# Branly_Pi_v2.net
KiCad netlist of a schematic drawn in EAGLE
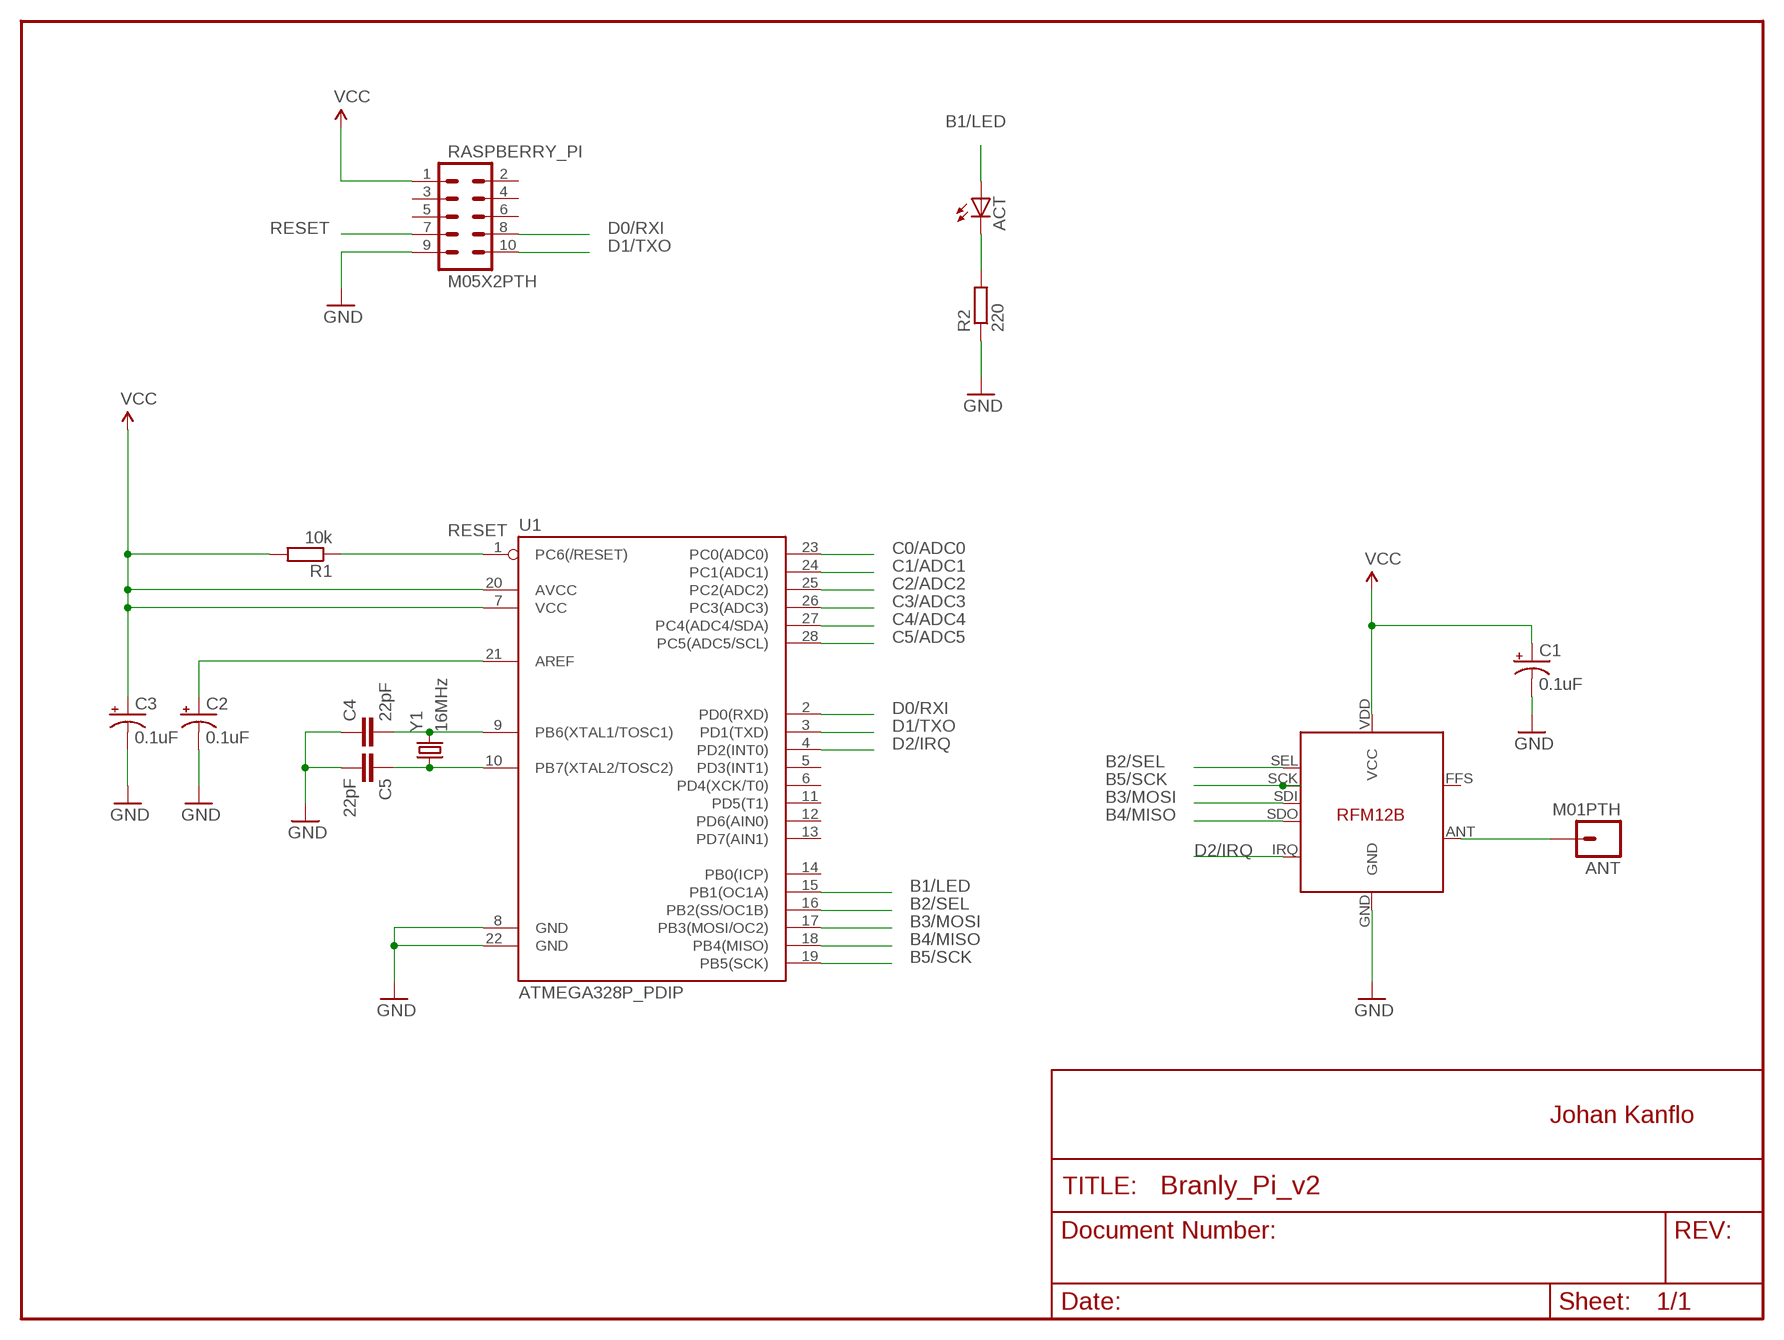
[diagram p0: schematic, sheet 1]

(export (version "E")
  (design (tool "Eeschema 10.0.6"))
  (components
    (comp (ref "ACT")
      (value "LED5MM")
      (footprint "eagle-import:LED5MM")
      (libsource (lib "eagle-import") (part "LED5MM"))
    )
    (comp (ref "ANT")
      (value "M01PTH")
      (footprint "eagle-import:1X01")
      (libsource (lib "eagle-import") (part "M01PTH"))
    )
    (comp (ref "C1")
      (value "0.1uF")
      (footprint "eagle-import:CPOL-RADIAL-10UF-25V")
      (libsource (lib "eagle-import") (part "CAP_POLPTH2"))
    )
    (comp (ref "C2")
      (value "0.1uF")
      (footprint "eagle-import:CPOL-RADIAL-10UF-25V")
      (libsource (lib "eagle-import") (part "CAP_POLPTH2"))
    )
    (comp (ref "C3")
      (value "0.1uF")
      (footprint "eagle-import:CPOL-RADIAL-10UF-25V")
      (libsource (lib "eagle-import") (part "CAP_POLPTH2"))
    )
    (comp (ref "C4")
      (value "22pF")
      (footprint "eagle-import:CAP-PTH-SMALL2")
      (libsource (lib "eagle-import") (part "CAPPTH2"))
    )
    (comp (ref "C5")
      (value "22pF")
      (footprint "eagle-import:CAP-PTH-SMALL2")
      (libsource (lib "eagle-import") (part "CAPPTH2"))
    )
    (comp (ref "R1")
      (value "10k")
      (footprint "eagle-import:0207_7")
      (libsource (lib "eagle-import") (part "R-EU_0207/7"))
    )
    (comp (ref "R2")
      (value "220")
      (footprint "eagle-import:0207_7")
      (libsource (lib "eagle-import") (part "R-EU_0207/7"))
    )
    (comp (ref "RASPBERRY_PI")
      (value "M05X2PTH")
      (footprint "eagle-import:AVR_ICSP")
      (libsource (lib "eagle-import") (part "M05X2PTH"))
    )
    (comp (ref "U1")
      (value "ATMEGA328P_PDIP")
      (footprint "eagle-import:DIL28-3")
      (libsource (lib "eagle-import") (part "ATMEGA328P_PDIP"))
    )
    (comp (ref "U2")
      (value "RFM12B")
      (footprint "eagle-import:RFM12B")
      (libsource (lib "eagle-import") (part "RFM12B"))
    )
    (comp (ref "Y1")
      (value "16MHz")
      (footprint "eagle-import:HC49US")
      (libsource (lib "eagle-import") (part "CRYSTALHC49US"))
    )
  )
  (nets
    (net (code "1") (name "/B1{slash}LED") (class "Default")
      (node (ref "ACT") (pin "A") (pinfunction "A_A") (pintype "passive"))
      (node (ref "U1") (pin "15") (pinfunction "PB1(OC1A)_15") (pintype "bidirectional"))
    )
    (net (code "2") (name "/B2{slash}SEL") (class "Default")
      (node (ref "U1") (pin "16") (pinfunction "PB2(SS/OC1B)_16") (pintype "bidirectional"))
      (node (ref "U2") (pin "SEL") (pinfunction "SEL_SEL") (pintype "input"))
    )
    (net (code "3") (name "/B3{slash}MOSI") (class "Default")
      (node (ref "U1") (pin "17") (pinfunction "PB3(MOSI/OC2)_17") (pintype "bidirectional"))
      (node (ref "U2") (pin "SDI") (pinfunction "SDI_SDI") (pintype "input"))
    )
    (net (code "4") (name "/B4{slash}MISO") (class "Default")
      (node (ref "U1") (pin "18") (pinfunction "PB4(MISO)_18") (pintype "bidirectional"))
      (node (ref "U2") (pin "SDO") (pinfunction "SDO_SDO") (pintype "output"))
    )
    (net (code "5") (name "/B5{slash}SCK") (class "Default")
      (node (ref "U1") (pin "19") (pinfunction "PB5(SCK)_19") (pintype "bidirectional"))
      (node (ref "U2") (pin "SCK") (pinfunction "SCK_SCK") (pintype "input"))
    )
    (net (code "6") (name "/C0{slash}ADC0") (class "Default")
      (node (ref "U1") (pin "23") (pinfunction "PC0(ADC0)_23") (pintype "bidirectional"))
    )
    (net (code "7") (name "/C1{slash}ADC1") (class "Default")
      (node (ref "U1") (pin "24") (pinfunction "PC1(ADC1)_24") (pintype "bidirectional"))
    )
    (net (code "8") (name "/C2{slash}ADC2") (class "Default")
      (node (ref "U1") (pin "25") (pinfunction "PC2(ADC2)_25") (pintype "bidirectional"))
    )
    (net (code "9") (name "/C3{slash}ADC3") (class "Default")
      (node (ref "U1") (pin "26") (pinfunction "PC3(ADC3)_26") (pintype "bidirectional"))
    )
    (net (code "10") (name "/C4{slash}ADC4") (class "Default")
      (node (ref "U1") (pin "27") (pinfunction "PC4(ADC4/SDA)_27") (pintype "bidirectional"))
    )
    (net (code "11") (name "/C5{slash}ADC5") (class "Default")
      (node (ref "U1") (pin "28") (pinfunction "PC5(ADC5/SCL)_28") (pintype "bidirectional"))
    )
    (net (code "12") (name "/D0{slash}RXI") (class "Default")
      (node (ref "RASPBERRY_PI") (pin "8") (pinfunction "8_8") (pintype "passive"))
      (node (ref "U1") (pin "2") (pinfunction "PD0(RXD)_2") (pintype "bidirectional"))
    )
    (net (code "13") (name "/D1{slash}TXO") (class "Default")
      (node (ref "RASPBERRY_PI") (pin "10") (pinfunction "10_10") (pintype "passive"))
      (node (ref "U1") (pin "3") (pinfunction "PD1(TXD)_3") (pintype "bidirectional"))
    )
    (net (code "14") (name "/D2{slash}IRQ") (class "Default")
      (node (ref "U1") (pin "4") (pinfunction "PD2(INT0)_4") (pintype "bidirectional"))
      (node (ref "U2") (pin "IRQ") (pinfunction "IRQ_IRQ") (pintype "open_collector"))
    )
    (net (code "15") (name "/RESET") (class "Default")
      (node (ref "R1") (pin "1") (pinfunction "1_1") (pintype "passive"))
      (node (ref "RASPBERRY_PI") (pin "7") (pinfunction "7_7") (pintype "passive"))
      (node (ref "U1") (pin "1") (pinfunction "PC6(/RESET)_1") (pintype "bidirectional"))
    )
    (net (code "16") (name "GND") (class "Default")
      (node (ref "C1") (pin "2") (pinfunction "-_2") (pintype "passive"))
      (node (ref "C2") (pin "2") (pinfunction "-_2") (pintype "passive"))
      (node (ref "C3") (pin "2") (pinfunction "-_2") (pintype "passive"))
      (node (ref "C4") (pin "1") (pinfunction "1_1") (pintype "passive"))
      (node (ref "C5") (pin "2") (pinfunction "2_2") (pintype "passive"))
      (node (ref "R2") (pin "1") (pinfunction "1_1") (pintype "passive"))
      (node (ref "RASPBERRY_PI") (pin "9") (pinfunction "9_9") (pintype "passive"))
      (node (ref "U1") (pin "22") (pinfunction "GND_22") (pintype "bidirectional"))
      (node (ref "U1") (pin "8") (pinfunction "GND_8") (pintype "bidirectional"))
      (node (ref "U2") (pin "GND") (pinfunction "GND_GND") (pintype "power_in"))
    )
    (net (code "17") (name "Net-(ACT-C)") (class "Default")
      (node (ref "ACT") (pin "K") (pinfunction "C_K") (pintype "passive"))
      (node (ref "R2") (pin "2") (pinfunction "2_2") (pintype "passive"))
    )
    (net (code "18") (name "Net-(ANT-Pad1)") (class "Default")
      (node (ref "ANT") (pin "1") (pinfunction "1_1") (pintype "passive"))
      (node (ref "U2") (pin "ANT") (pinfunction "ANT_ANT") (pintype "passive"))
    )
    (net (code "19") (name "Net-(C2-+)") (class "Default")
      (node (ref "C2") (pin "1") (pinfunction "+_1") (pintype "passive"))
      (node (ref "U1") (pin "21") (pinfunction "AREF_21") (pintype "bidirectional"))
    )
    (net (code "20") (name "Net-(U1-PB6(XTAL1{slash}TOSC1))") (class "Default")
      (node (ref "C4") (pin "2") (pinfunction "2_2") (pintype "passive"))
      (node (ref "U1") (pin "9") (pinfunction "PB6(XTAL1/TOSC1)_9") (pintype "bidirectional"))
      (node (ref "Y1") (pin "2") (pinfunction "2_2") (pintype "passive"))
    )
    (net (code "21") (name "Net-(U1-PB7(XTAL2{slash}TOSC2))") (class "Default")
      (node (ref "C5") (pin "1") (pinfunction "1_1") (pintype "passive"))
      (node (ref "U1") (pin "10") (pinfunction "PB7(XTAL2/TOSC2)_10") (pintype "bidirectional"))
      (node (ref "Y1") (pin "1") (pinfunction "1_1") (pintype "passive"))
    )
    (net (code "22") (name "VCC") (class "Default")
      (node (ref "C1") (pin "1") (pinfunction "+_1") (pintype "passive"))
      (node (ref "C3") (pin "1") (pinfunction "+_1") (pintype "passive"))
      (node (ref "R1") (pin "2") (pinfunction "2_2") (pintype "passive"))
      (node (ref "RASPBERRY_PI") (pin "1") (pinfunction "1_1") (pintype "passive"))
      (node (ref "U1") (pin "20") (pinfunction "AVCC_20") (pintype "bidirectional"))
      (node (ref "U1") (pin "7") (pinfunction "VCC_7") (pintype "bidirectional"))
      (node (ref "U2") (pin "VDD") (pinfunction "VCC_VDD") (pintype "power_in"))
    )
    (net (code "23") (name "unconnected-(RASPBERRY_PI-Pad2)") (class "Default")
      (node (ref "RASPBERRY_PI") (pin "2") (pinfunction "2_2") (pintype "passive"))
    )
    (net (code "24") (name "unconnected-(RASPBERRY_PI-Pad3)") (class "Default")
      (node (ref "RASPBERRY_PI") (pin "3") (pinfunction "3_3") (pintype "passive"))
    )
    (net (code "25") (name "unconnected-(RASPBERRY_PI-Pad4)") (class "Default")
      (node (ref "RASPBERRY_PI") (pin "4") (pinfunction "4_4") (pintype "passive"))
    )
    (net (code "26") (name "unconnected-(RASPBERRY_PI-Pad5)") (class "Default")
      (node (ref "RASPBERRY_PI") (pin "5") (pinfunction "5_5") (pintype "passive"))
    )
    (net (code "27") (name "unconnected-(RASPBERRY_PI-Pad6)") (class "Default")
      (node (ref "RASPBERRY_PI") (pin "6") (pinfunction "6_6") (pintype "passive"))
    )
    (net (code "28") (name "unconnected-(U1-PB0(ICP)-Pad14)") (class "Default")
      (node (ref "U1") (pin "14") (pinfunction "PB0(ICP)_14") (pintype "bidirectional"))
    )
    (net (code "29") (name "unconnected-(U1-PD3(INT1)-Pad5)") (class "Default")
      (node (ref "U1") (pin "5") (pinfunction "PD3(INT1)_5") (pintype "bidirectional"))
    )
    (net (code "30") (name "unconnected-(U1-PD4(XCK{slash}T0)-Pad6)") (class "Default")
      (node (ref "U1") (pin "6") (pinfunction "PD4(XCK/T0)_6") (pintype "bidirectional"))
    )
    (net (code "31") (name "unconnected-(U1-PD5(T1)-Pad11)") (class "Default")
      (node (ref "U1") (pin "11") (pinfunction "PD5(T1)_11") (pintype "bidirectional"))
    )
    (net (code "32") (name "unconnected-(U1-PD6(AIN0)-Pad12)") (class "Default")
      (node (ref "U1") (pin "12") (pinfunction "PD6(AIN0)_12") (pintype "bidirectional"))
    )
    (net (code "33") (name "unconnected-(U1-PD7(AIN1)-Pad13)") (class "Default")
      (node (ref "U1") (pin "13") (pinfunction "PD7(AIN1)_13") (pintype "bidirectional"))
    )
    (net (code "34") (name "unconnected-(U2-PadFFS)") (class "Default")
      (node (ref "U2") (pin "FFS") (pinfunction "FFS_FFS") (pintype "bidirectional"))
    )
  )
)
